# SCH_555-circuit_2025-10-19.net
KiCad netlist of a schematic drawn in EasyEDA
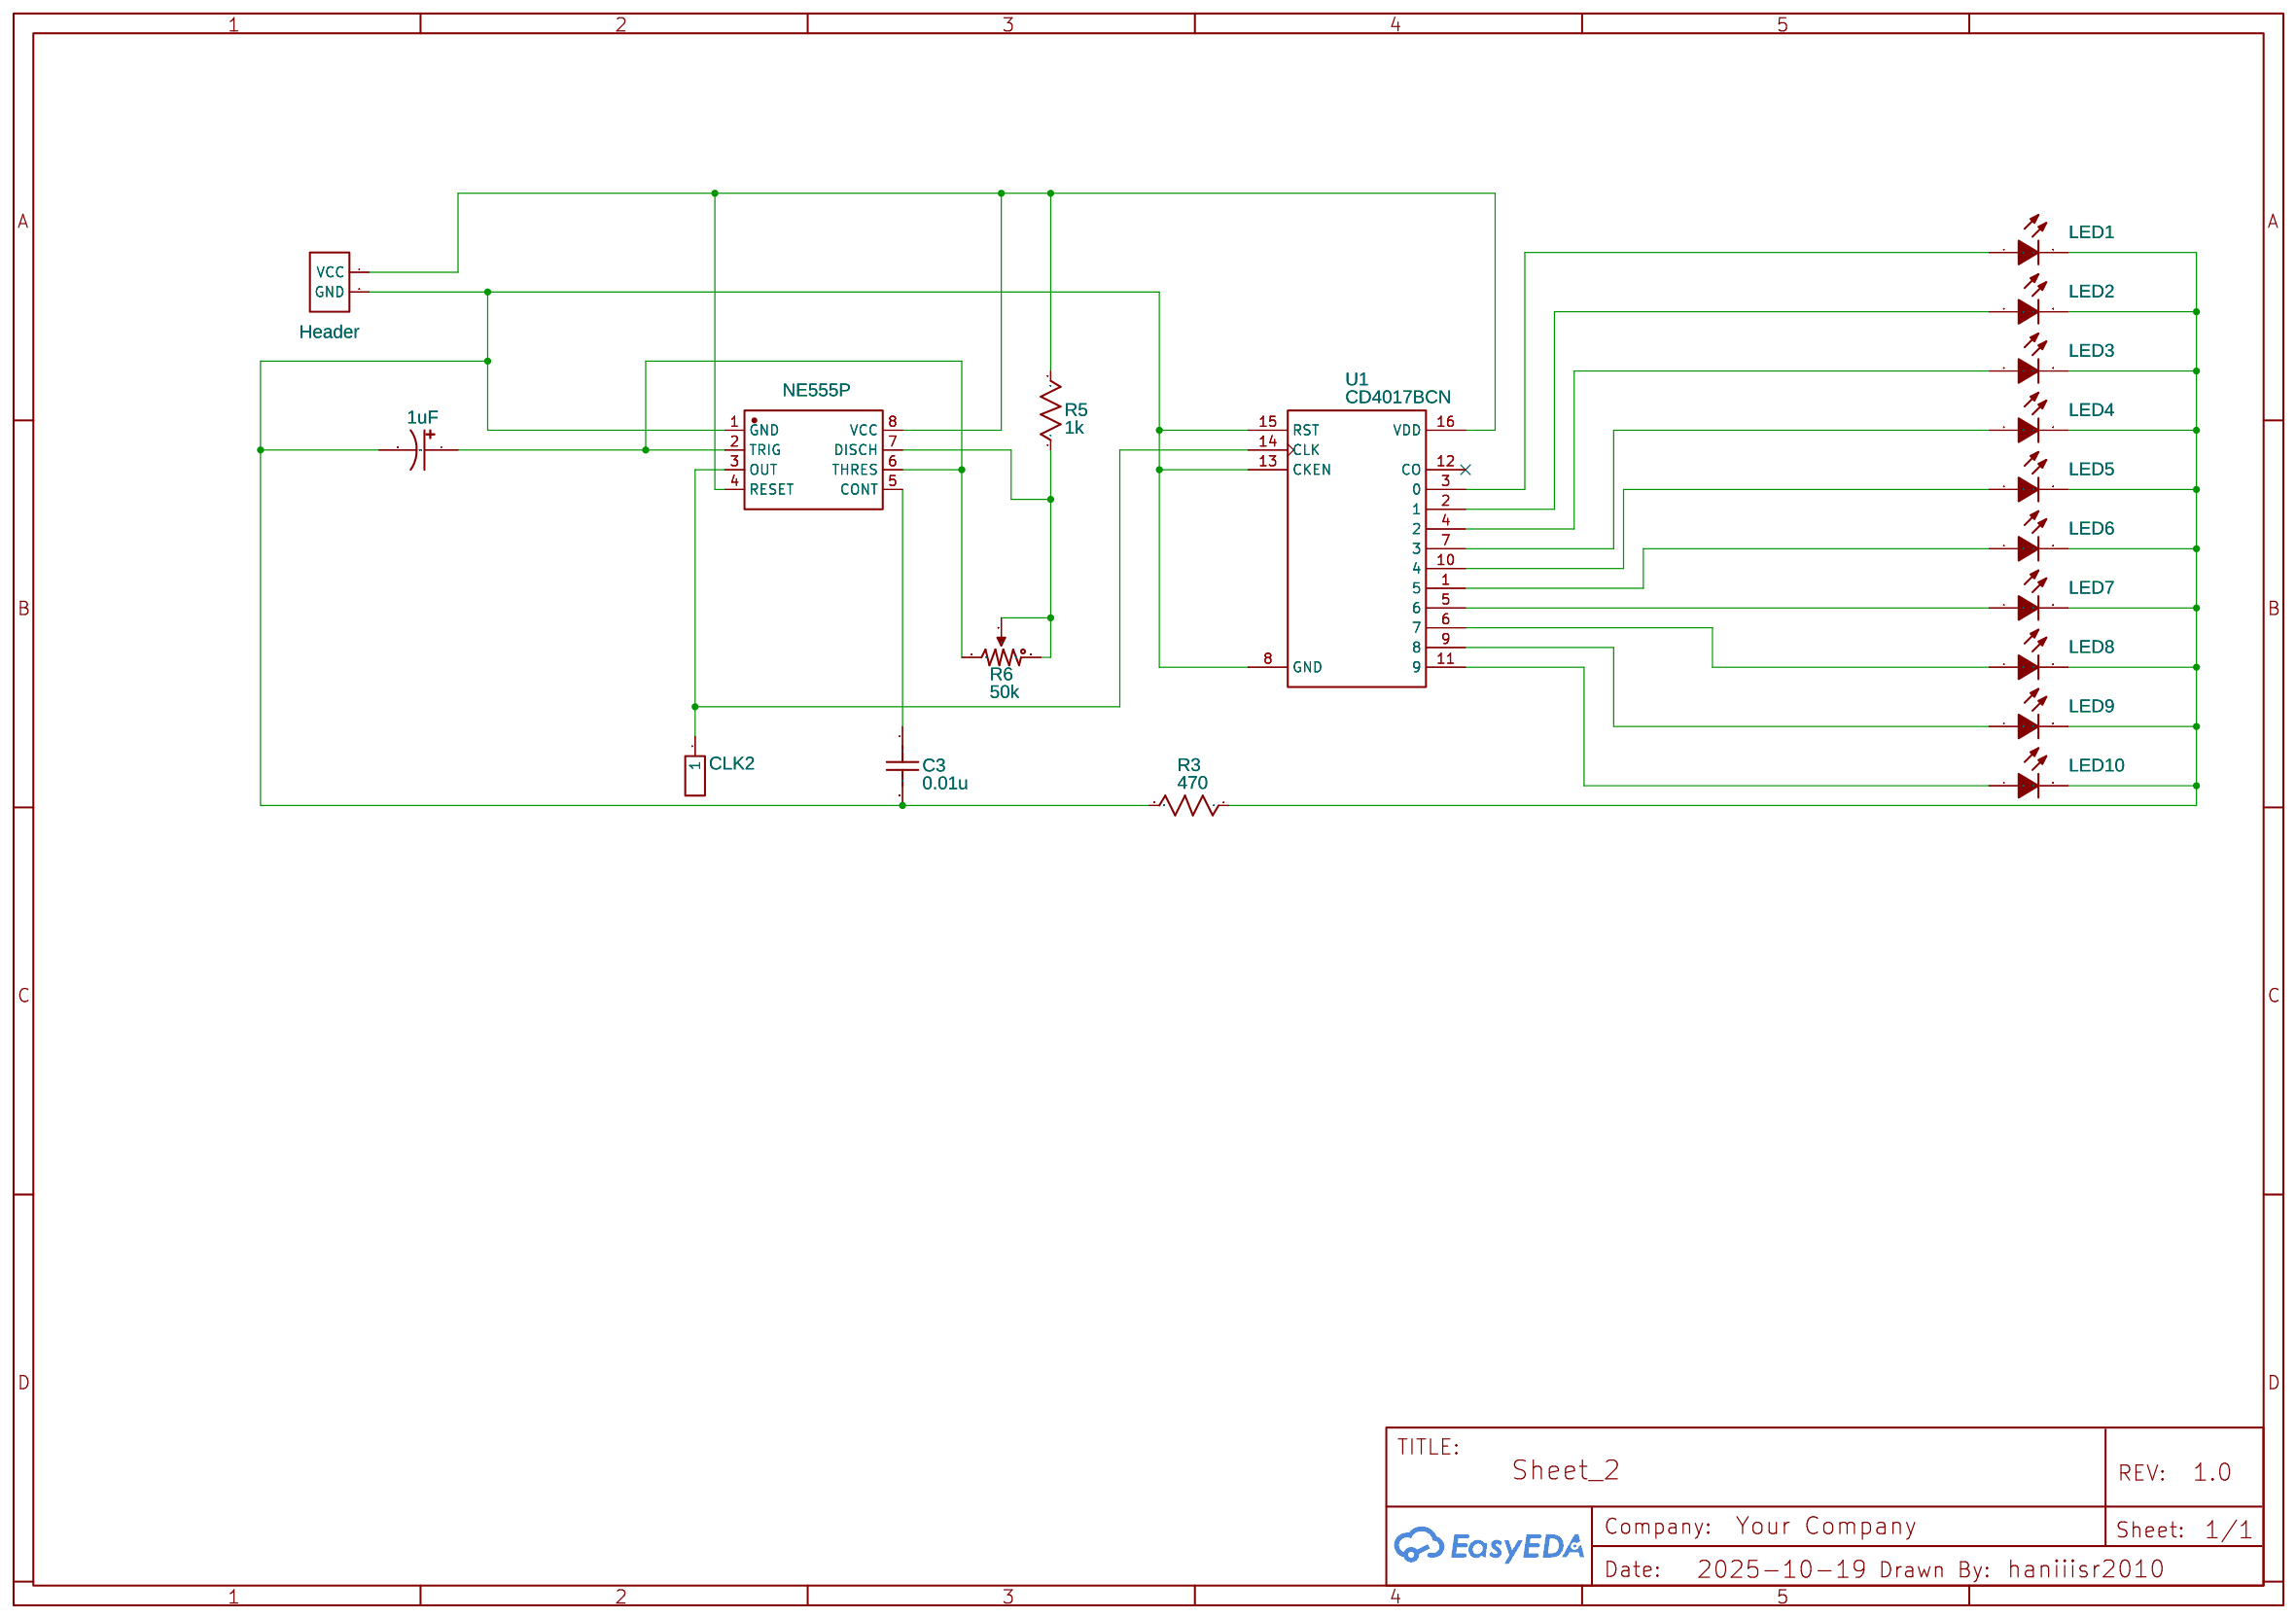
[diagram p0: schematic sheet]

(export (version "E")
  (design (tool "Eeschema 10.0.6"))
  (components
    (comp (ref "C3") (value "0.01u") (libsource (lib "") (part "C_0603_US")))
    (comp (ref "C4")
      (value "1uF")
      (fields (field (name "Manufacturer Part") "UVZ1H010MDD") (field (name "Manufacturer") "Nichicon(尼吉康)"))
      (libsource (lib "") (part "UVZ1H010MDD"))
    )
    (comp (ref "CLK2")
      (value "C81276")
      (fields
        (field (name "Manufacturer Part") "2.54-1*1P针")
        (field (name "Manufacturer") "BOOMELE(Boom Precision Elec)")
      )
      (libsource (lib "") (part "Header-Male-2.54_1x1"))
    )
    (comp (ref "H2") (value "Header") (libsource (lib "") (part "HEADER-FEMALE-2.54_1X2")))
    (comp (ref "LED1") (value "LED_5MM") (libsource (lib "") (part "LED_5MM")))
    (comp (ref "LED2") (value "LED_5MM") (libsource (lib "") (part "LED_5MM")))
    (comp (ref "LED3") (value "LED_5MM") (libsource (lib "") (part "LED_5MM")))
    (comp (ref "LED4") (value "LED_5MM") (libsource (lib "") (part "LED_5MM")))
    (comp (ref "LED5") (value "LED_5MM") (libsource (lib "") (part "LED_5MM")))
    (comp (ref "LED6") (value "LED_5MM") (libsource (lib "") (part "LED_5MM")))
    (comp (ref "LED7") (value "LED_5MM") (libsource (lib "") (part "LED_5MM")))
    (comp (ref "LED8") (value "LED_5MM") (libsource (lib "") (part "LED_5MM")))
    (comp (ref "LED9") (value "LED_5MM") (libsource (lib "") (part "LED_5MM")))
    (comp (ref "LED10") (value "LED_5MM") (libsource (lib "") (part "LED_5MM")))
    (comp (ref "R3")
      (value "470")
      (fields (field (name "Manufacturer Part") "?"))
      (libsource (lib "") (part "Resistor"))
    )
    (comp (ref "R5")
      (value "1k")
      (fields (field (name "Manufacturer Part") "?"))
      (libsource (lib "") (part "Resistor_1"))
    )
    (comp (ref "R6")
      (value "50k")
      (fields (field (name "Manufacturer Part") "?"))
      (libsource (lib "") (part "Potentiometer"))
    )
    (comp (ref "U1") (value "CD4017BCN") (libsource (lib "") (part "CD4017BCN")))
    (comp (ref "U3")
      (value "NE555P")
      (fields (field (name "Manufacturer") "TI(德州仪器)"))
      (libsource (lib "") (part "NE555P"))
    )
  )
  (nets
    (net (code "1") (name "Net-(H2-GND)") (class "Default")
      (node (ref "C3") (pin "2") (pinfunction "2_2") (pintype "unspecified"))
      (node (ref "C4") (pin "2") (pinfunction "2_2") (pintype "unspecified"))
      (node (ref "H2") (pin "2") (pinfunction "GND_2") (pintype "unspecified"))
      (node (ref "R3") (pin "2") (pinfunction "2_2") (pintype "unspecified"))
      (node (ref "U1") (pin "13") (pinfunction "CKEN_13") (pintype "unspecified"))
      (node (ref "U1") (pin "15") (pinfunction "RST_15") (pintype "unspecified"))
      (node (ref "U1") (pin "8") (pinfunction "GND_8") (pintype "passive"))
      (node (ref "U3") (pin "1") (pinfunction "GND_1") (pintype "unspecified"))
    )
    (net (code "2") (name "Net-(H2-VCC)") (class "Default")
      (node (ref "H2") (pin "1") (pinfunction "VCC_1") (pintype "unspecified"))
      (node (ref "R5") (pin "2") (pinfunction "2_2") (pintype "unspecified"))
      (node (ref "U1") (pin "16") (pinfunction "VDD_16") (pintype "passive"))
      (node (ref "U3") (pin "4") (pinfunction "RESET_4") (pintype "unspecified"))
      (node (ref "U3") (pin "8") (pinfunction "VCC_8") (pintype "unspecified"))
    )
    (net (code "3") (name "Net-(LED1-A)") (class "Default")
      (node (ref "LED1") (pin "1") (pinfunction "A_1") (pintype "input"))
      (node (ref "U1") (pin "3") (pinfunction "0_3") (pintype "output"))
    )
    (net (code "4") (name "Net-(LED1-K)") (class "Default")
      (node (ref "LED1") (pin "2") (pinfunction "K_2") (pintype "input"))
      (node (ref "LED10") (pin "2") (pinfunction "K_2") (pintype "input"))
      (node (ref "LED2") (pin "2") (pinfunction "K_2") (pintype "input"))
      (node (ref "LED3") (pin "2") (pinfunction "K_2") (pintype "input"))
      (node (ref "LED4") (pin "2") (pinfunction "K_2") (pintype "input"))
      (node (ref "LED5") (pin "2") (pinfunction "K_2") (pintype "input"))
      (node (ref "LED6") (pin "2") (pinfunction "K_2") (pintype "input"))
      (node (ref "LED7") (pin "2") (pinfunction "K_2") (pintype "input"))
      (node (ref "LED8") (pin "2") (pinfunction "K_2") (pintype "input"))
      (node (ref "LED9") (pin "2") (pinfunction "K_2") (pintype "input"))
      (node (ref "R3") (pin "1") (pinfunction "1_1") (pintype "unspecified"))
    )
    (net (code "5") (name "Net-(LED2-A)") (class "Default")
      (node (ref "LED2") (pin "1") (pinfunction "A_1") (pintype "input"))
      (node (ref "U1") (pin "2") (pinfunction "1_2") (pintype "output"))
    )
    (net (code "6") (name "Net-(LED3-A)") (class "Default")
      (node (ref "LED3") (pin "1") (pinfunction "A_1") (pintype "input"))
      (node (ref "U1") (pin "4") (pinfunction "2_4") (pintype "output"))
    )
    (net (code "7") (name "Net-(LED4-A)") (class "Default")
      (node (ref "LED4") (pin "1") (pinfunction "A_1") (pintype "input"))
      (node (ref "U1") (pin "7") (pinfunction "3_7") (pintype "output"))
    )
    (net (code "8") (name "Net-(LED5-A)") (class "Default")
      (node (ref "LED5") (pin "1") (pinfunction "A_1") (pintype "input"))
      (node (ref "U1") (pin "10") (pinfunction "4_10") (pintype "output"))
    )
    (net (code "9") (name "Net-(LED6-A)") (class "Default")
      (node (ref "LED6") (pin "1") (pinfunction "A_1") (pintype "input"))
      (node (ref "U1") (pin "1") (pinfunction "5_1") (pintype "output"))
    )
    (net (code "10") (name "Net-(LED7-A)") (class "Default")
      (node (ref "LED7") (pin "1") (pinfunction "A_1") (pintype "input"))
      (node (ref "U1") (pin "5") (pinfunction "6_5") (pintype "output"))
    )
    (net (code "11") (name "Net-(LED8-A)") (class "Default")
      (node (ref "LED8") (pin "1") (pinfunction "A_1") (pintype "input"))
      (node (ref "U1") (pin "6") (pinfunction "7_6") (pintype "output"))
    )
    (net (code "12") (name "Net-(LED9-A)") (class "Default")
      (node (ref "LED9") (pin "1") (pinfunction "A_1") (pintype "input"))
      (node (ref "U1") (pin "9") (pinfunction "8_9") (pintype "output"))
    )
    (net (code "13") (name "Net-(LED10-A)") (class "Default")
      (node (ref "LED10") (pin "1") (pinfunction "A_1") (pintype "input"))
      (node (ref "U1") (pin "11") (pinfunction "9_11") (pintype "output"))
    )
    (net (code "14") (name "Net-(R6-2)") (class "Default")
      (node (ref "R5") (pin "1") (pinfunction "1_1") (pintype "unspecified"))
      (node (ref "R6") (pin "2") (pinfunction "3_2") (pintype "unspecified"))
      (node (ref "R6") (pin "3") (pinfunction "2_3") (pintype "unspecified"))
      (node (ref "U3") (pin "7") (pinfunction "DISCH_7") (pintype "unspecified"))
    )
    (net (code "15") (name "Net-(U1-CLK)") (class "Default")
      (node (ref "CLK2") (pin "1") (pinfunction "1_1") (pintype "unspecified"))
      (node (ref "U1") (pin "14") (pinfunction "CLK_14") (pintype "unspecified"))
      (node (ref "U3") (pin "3") (pinfunction "OUT_3") (pintype "unspecified"))
    )
    (net (code "16") (name "Net-(U3-CONT)") (class "Default")
      (node (ref "C3") (pin "1") (pinfunction "1_1") (pintype "unspecified"))
      (node (ref "U3") (pin "5") (pinfunction "CONT_5") (pintype "unspecified"))
    )
    (net (code "17") (name "Net-(U3-THRES)") (class "Default")
      (node (ref "C4") (pin "1") (pinfunction "1_1") (pintype "unspecified"))
      (node (ref "R6") (pin "1") (pinfunction "1_1") (pintype "unspecified"))
      (node (ref "U3") (pin "2") (pinfunction "TRIG_2") (pintype "unspecified"))
      (node (ref "U3") (pin "6") (pinfunction "THRES_6") (pintype "unspecified"))
    )
    (net (code "18") (name "unconnected-(U1-CO-Pad12)") (class "Default")
      (node (ref "U1") (pin "12") (pinfunction "CO_12") (pintype "output+no_connect"))
    )
  )
)
